# SPI_Breakout.net
KiCad netlist of a schematic drawn in Altium Designer
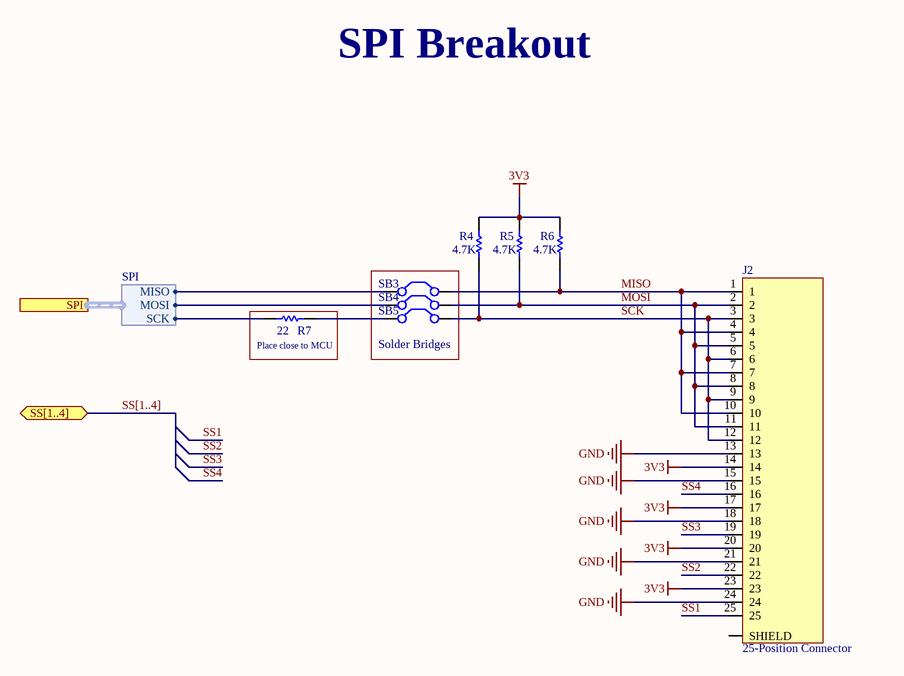
[diagram p0: SPI_Breakout.SchDoc]

(export (version "E")
  (design (tool "Eeschema 10.0.6"))
  (components
    (comp (ref "J2")
      (value "25-Position Connector")
      (footprint "25-POS D-SUB")
      (fields
        (field (name "DIGIKEY PART NUMBER") "NOR1066-ND")
        (field (name "MANUFACTURER PART NUMBER") "772-E25-213R051")
      )
      (libsource (lib "LaunchyRIOComponents") (part "25-Position Connector"))
    )
    (comp (ref "R4")
      (value "4.7K")
      (footprint "0402")
      (description "Resistor")
      (fields (field (name "Comment") "Res1"))
      (libsource (lib "Miscellaneous Devices") (part "Res1"))
    )
    (comp (ref "R5")
      (value "4.7K")
      (footprint "0402")
      (description "Resistor")
      (fields (field (name "Comment") "Res1"))
      (libsource (lib "Miscellaneous Devices") (part "Res1"))
    )
    (comp (ref "R6")
      (value "4.7K")
      (footprint "0402")
      (description "Resistor")
      (fields (field (name "Comment") "Res1"))
      (libsource (lib "Miscellaneous Devices") (part "Res1"))
    )
    (comp (ref "R7")
      (value "22")
      (footprint "0402")
      (description "Resistor")
      (fields (field (name "Comment") "Res1"))
      (libsource (lib "Miscellaneous Devices") (part "Res1"))
    )
    (comp (ref "SB3")
      (value "Solder Bridge")
      (footprint "SB-2pos")
      (description "Jumper Wire")
      (libsource (lib "Miscellaneous Devices") (part "Jumper"))
    )
    (comp (ref "SB4")
      (value "Solder Bridge")
      (footprint "SB-2pos")
      (description "Jumper Wire")
      (libsource (lib "Miscellaneous Devices") (part "Jumper"))
    )
    (comp (ref "SB5")
      (value "Solder Bridge")
      (footprint "SB-2pos")
      (description "Jumper Wire")
      (libsource (lib "Miscellaneous Devices") (part "Jumper"))
    )
  )
  (nets
    (net (code "2") (name "/MISO") (class "Default")
      (node (ref "J2") (pin "1") (pinfunction "1_1") (pintype "bidirectional"))
      (node (ref "J2") (pin "10") (pinfunction "10_10") (pintype "bidirectional"))
      (node (ref "J2") (pin "4") (pinfunction "4_4") (pintype "bidirectional"))
      (node (ref "J2") (pin "7") (pinfunction "7_7") (pintype "bidirectional"))
      (node (ref "R6") (pin "2") (pinfunction "2_2") (pintype "passive"))
      (node (ref "SB3") (pin "2") (pinfunction "C2_2") (pintype "passive"))
    )
    (net (code "3") (name "/MOSI") (class "Default")
      (node (ref "J2") (pin "11") (pinfunction "11_11") (pintype "bidirectional"))
      (node (ref "J2") (pin "2") (pinfunction "2_2") (pintype "bidirectional"))
      (node (ref "J2") (pin "5") (pinfunction "5_5") (pintype "bidirectional"))
      (node (ref "J2") (pin "8") (pinfunction "8_8") (pintype "bidirectional"))
      (node (ref "R5") (pin "1") (pinfunction "1_1") (pintype "passive"))
      (node (ref "SB4") (pin "2") (pinfunction "C2_2") (pintype "passive"))
    )
    (net (code "4") (name "/SCK") (class "Default")
      (node (ref "J2") (pin "12") (pinfunction "12_12") (pintype "bidirectional"))
      (node (ref "J2") (pin "3") (pinfunction "3_3") (pintype "bidirectional"))
      (node (ref "J2") (pin "6") (pinfunction "6_6") (pintype "bidirectional"))
      (node (ref "J2") (pin "9") (pinfunction "9_9") (pintype "bidirectional"))
      (node (ref "R4") (pin "2") (pinfunction "2_2") (pintype "passive"))
      (node (ref "SB5") (pin "2") (pinfunction "C2_2") (pintype "passive"))
    )
    (net (code "5") (name "/SS1") (class "Default")
      (node (ref "J2") (pin "25") (pinfunction "25_25") (pintype "bidirectional"))
    )
    (net (code "6") (name "/SS2") (class "Default")
      (node (ref "J2") (pin "22") (pinfunction "22_22") (pintype "bidirectional"))
    )
    (net (code "7") (name "/SS3") (class "Default")
      (node (ref "J2") (pin "19") (pinfunction "19_19") (pintype "bidirectional"))
    )
    (net (code "8") (name "/SS4") (class "Default")
      (node (ref "J2") (pin "16") (pinfunction "16_16") (pintype "bidirectional"))
    )
    (net (code "11") (name "3V3") (class "Default")
      (node (ref "J2") (pin "14") (pinfunction "14_14") (pintype "bidirectional"))
      (node (ref "J2") (pin "17") (pinfunction "17_17") (pintype "bidirectional"))
      (node (ref "J2") (pin "20") (pinfunction "20_20") (pintype "bidirectional"))
      (node (ref "J2") (pin "23") (pinfunction "23_23") (pintype "bidirectional"))
      (node (ref "R4") (pin "1") (pinfunction "1_1") (pintype "passive"))
      (node (ref "R5") (pin "2") (pinfunction "2_2") (pintype "passive"))
      (node (ref "R6") (pin "1") (pinfunction "1_1") (pintype "passive"))
    )
    (net (code "12") (name "GND") (class "Default")
      (node (ref "J2") (pin "13") (pinfunction "13_13") (pintype "bidirectional"))
      (node (ref "J2") (pin "15") (pinfunction "15_15") (pintype "bidirectional"))
      (node (ref "J2") (pin "18") (pinfunction "18_18") (pintype "bidirectional"))
      (node (ref "J2") (pin "21") (pinfunction "21_21") (pintype "bidirectional"))
      (node (ref "J2") (pin "24") (pinfunction "24_24") (pintype "bidirectional"))
    )
    (net (code "13") (name "Net-(SB5-C1)") (class "Default")
      (node (ref "R7") (pin "2") (pinfunction "2_2") (pintype "passive"))
      (node (ref "SB5") (pin "1") (pinfunction "C1_1") (pintype "passive"))
    )
    (net (code "14") (name "unconnected-(J2-PadSHIELD)") (class "Default")
      (node (ref "J2") (pin "SHIELD") (pinfunction "SHIELD_SHIELD") (pintype "passive"))
    )
    (net (code "15") (name "unconnected-(R7-Pad1)") (class "Default")
      (node (ref "R7") (pin "1") (pinfunction "1_1") (pintype "passive"))
    )
    (net (code "16") (name "unconnected-(SB3-C1-Pad1)") (class "Default")
      (node (ref "SB3") (pin "1") (pinfunction "C1_1") (pintype "passive"))
    )
    (net (code "17") (name "unconnected-(SB4-C1-Pad1)") (class "Default")
      (node (ref "SB4") (pin "1") (pinfunction "C1_1") (pintype "passive"))
    )
  )
)
